# timer.net
KiCad netlist of a schematic drawn in EAGLE
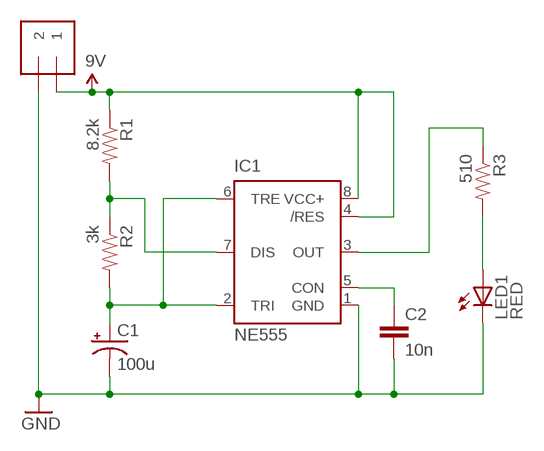
[diagram p0: schematic, sheet 1]

(export (version "E")
  (design (tool "Eeschema 10.0.6"))
  (components
    (comp (ref "9V")
      (value "VCC+")
      (footprint "eagle-import:1X2-3.5MM")
      (libsource (lib "eagle-import") (part "1X2-3.5MM"))
    )
    (comp (ref "C1")
      (value "100u")
      (footprint "eagle-import:CPOL-RADIAL-100UF-25V")
      (libsource (lib "eagle-import") (part "CAP_POLPTH1"))
    )
    (comp (ref "C2")
      (value "10n")
      (footprint "eagle-import:CAP-PTH-SMALL")
      (libsource (lib "eagle-import") (part "CAPPTH"))
    )
    (comp (ref "IC1")
      (value "NE555")
      (footprint "eagle-import:DIL-08")
      (fields (field (name "MF") "Arrow Electronics") (field (name "MPN") "NE555N"))
      (libsource (lib "eagle-import") (part "NE555"))
    )
    (comp (ref "LED1")
      (value "RED")
      (footprint "eagle-import:LED5MM")
      (libsource (lib "eagle-import") (part "LED5MM"))
    )
    (comp (ref "R1")
      (value "8.2k")
      (footprint "eagle-import:AXIAL-0.3")
      (libsource (lib "eagle-import") (part "RESISTORAXIAL-0.3"))
    )
    (comp (ref "R2")
      (value "3k")
      (footprint "eagle-import:AXIAL-0.3")
      (libsource (lib "eagle-import") (part "RESISTORAXIAL-0.3"))
    )
    (comp (ref "R3")
      (value "510")
      (footprint "eagle-import:AXIAL-0.3")
      (libsource (lib "eagle-import") (part "RESISTORAXIAL-0.3"))
    )
  )
  (nets
    (net (code "1") (name "9V") (class "Default")
      (node (ref "9V") (pin "1") (pinfunction "1_1") (pintype "passive"))
      (node (ref "IC1") (pin "4") (pinfunction "/RES_4") (pintype "input"))
      (node (ref "IC1") (pin "8") (pinfunction "VCC+_8") (pintype "power_in"))
      (node (ref "R1") (pin "P$1") (pinfunction "1_P$1") (pintype "passive"))
    )
    (net (code "2") (name "GND") (class "Default")
      (node (ref "9V") (pin "2") (pinfunction "2_2") (pintype "passive"))
      (node (ref "C1") (pin "2") (pinfunction "-_2") (pintype "passive"))
      (node (ref "C2") (pin "2") (pinfunction "2_2") (pintype "passive"))
      (node (ref "IC1") (pin "1") (pinfunction "GND_1") (pintype "power_in"))
      (node (ref "LED1") (pin "K") (pinfunction "C_K") (pintype "passive"))
    )
    (net (code "3") (name "Net-(C1-+)") (class "Default")
      (node (ref "C1") (pin "1") (pinfunction "+_1") (pintype "passive"))
      (node (ref "IC1") (pin "2") (pinfunction "TRI_2") (pintype "input"))
      (node (ref "IC1") (pin "6") (pinfunction "TRE_6") (pintype "input"))
      (node (ref "R2") (pin "P$2") (pinfunction "2_P$2") (pintype "passive"))
    )
    (net (code "4") (name "Net-(IC1-CON)") (class "Default")
      (node (ref "C2") (pin "1") (pinfunction "1_1") (pintype "passive"))
      (node (ref "IC1") (pin "5") (pinfunction "CON_5") (pintype "input"))
    )
    (net (code "5") (name "Net-(IC1-DIS)") (class "Default")
      (node (ref "IC1") (pin "7") (pinfunction "DIS_7") (pintype "input"))
      (node (ref "R1") (pin "P$2") (pinfunction "2_P$2") (pintype "passive"))
      (node (ref "R2") (pin "P$1") (pinfunction "1_P$1") (pintype "passive"))
    )
    (net (code "6") (name "Net-(IC1-OUT)") (class "Default")
      (node (ref "IC1") (pin "3") (pinfunction "OUT_3") (pintype "output"))
      (node (ref "R3") (pin "P$1") (pinfunction "1_P$1") (pintype "passive"))
    )
    (net (code "7") (name "Net-(R3-2)") (class "Default")
      (node (ref "LED1") (pin "A") (pinfunction "A_A") (pintype "passive"))
      (node (ref "R3") (pin "P$2") (pinfunction "2_P$2") (pintype "passive"))
    )
  )
)
